# precharger_rev3.net
KiCad netlist of a schematic drawn in EAGLE
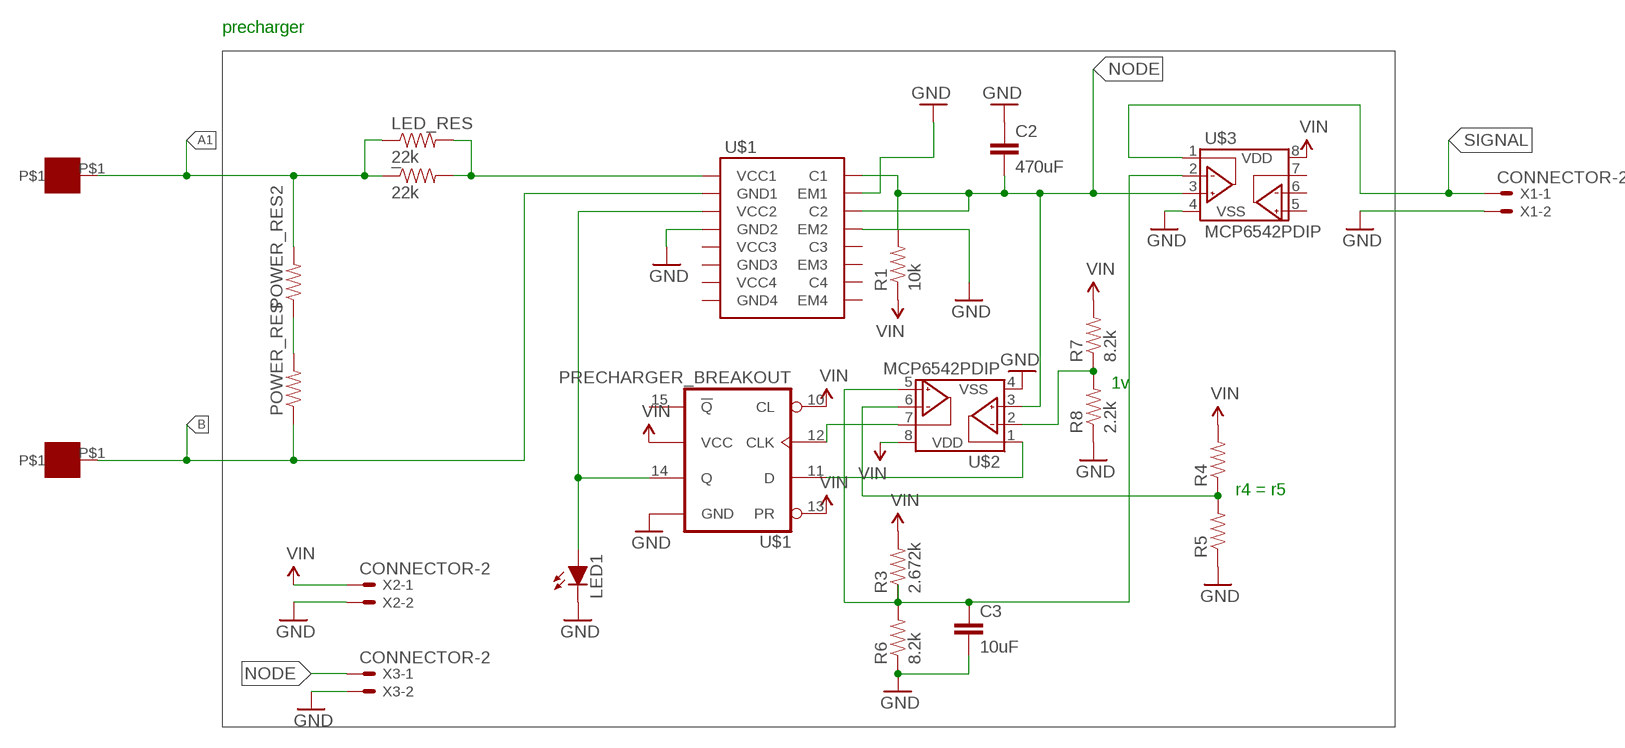
[diagram p0: schematic, sheet 1]

(export (version "E")
  (design (tool "Eeschema 10.0.6"))
  (components
    (comp (ref "+")
      (value "SOLDER_PAD")
      (footprint "eagle-import:SOLDER_PAD_XSMALL")
      (libsource (lib "eagle-import") (part "SOLDER_PAD"))
    )
    (comp (ref "-")
      (value "SOLDER_PAD")
      (footprint "eagle-import:SOLDER_PAD_XSMALL")
      (libsource (lib "eagle-import") (part "SOLDER_PAD"))
    )
    (comp (ref "C2")
      (value "470uF")
      (footprint "eagle-import:CAP-PTH-5MM")
      (libsource (lib "eagle-import") (part "CAPPTH1"))
    )
    (comp (ref "C3")
      (value "10uF")
      (footprint "eagle-import:CAP-PTH-SMALL")
      (libsource (lib "eagle-import") (part "CAPPTH"))
    )
    (comp (ref "LED1")
      (value "LED-3MM")
      (footprint "eagle-import:LED-3MM")
      (libsource (lib "eagle-import") (part "LED-3MM"))
    )
    (comp (ref "LED_RES")
      (value "22k")
      (footprint "eagle-import:AXIAL-0.3")
      (libsource (lib "eagle-import") (part "RESISTORAXIAL-0.3"))
    )
    (comp (ref "POWER_RES")
      (value "RESISTOR10W")
      (footprint "eagle-import:10W_RESISTOR_VISHAY")
      (libsource (lib "eagle-import") (part "RESISTOR10W"))
    )
    (comp (ref "POWER_RES2")
      (value "RESISTOR10W")
      (footprint "eagle-import:10W_RESISTOR_VISHAY")
      (libsource (lib "eagle-import") (part "RESISTOR10W"))
    )
    (comp (ref "R1")
      (value "10k")
      (footprint "eagle-import:AXIAL-0.3")
      (libsource (lib "eagle-import") (part "RESISTORAXIAL-0.3"))
    )
    (comp (ref "R3")
      (value "2.672k")
      (footprint "eagle-import:AXIAL-0.3")
      (libsource (lib "eagle-import") (part "RESISTORAXIAL-0.3"))
    )
    (comp (ref "R4")
      (value "RESISTORAXIAL-0.3")
      (footprint "eagle-import:AXIAL-0.3")
      (libsource (lib "eagle-import") (part "RESISTORAXIAL-0.3"))
    )
    (comp (ref "R5")
      (value "RESISTORAXIAL-0.3")
      (footprint "eagle-import:AXIAL-0.3")
      (libsource (lib "eagle-import") (part "RESISTORAXIAL-0.3"))
    )
    (comp (ref "R6")
      (value "8.2k")
      (footprint "eagle-import:AXIAL-0.3")
      (libsource (lib "eagle-import") (part "RESISTORAXIAL-0.3"))
    )
    (comp (ref "R7")
      (value "8.2k")
      (footprint "eagle-import:AXIAL-0.3")
      (libsource (lib "eagle-import") (part "RESISTORAXIAL-0.3"))
    )
    (comp (ref "R8")
      (value "2.2k")
      (footprint "eagle-import:AXIAL-0.3")
      (libsource (lib "eagle-import") (part "RESISTORAXIAL-0.3"))
    )
    (comp (ref "U$1")
      (value "PRECHARGER_BREAKOUT")
      (footprint "eagle-import:PRECHARGER_BREAKOUT")
      (libsource (lib "eagle-import") (part "PRECHARGER_BREAKOUT"))
    )
    (comp (ref "U$2")
      (value "MCP6542PDIP")
      (footprint "eagle-import:DIL08")
      (libsource (lib "eagle-import") (part "MCP6542PDIP"))
    )
    (comp (ref "U$3")
      (value "MCP6542PDIP")
      (footprint "eagle-import:DIL08")
      (libsource (lib "eagle-import") (part "MCP6542PDIP"))
    )
    (comp (ref "X1")
      (value "CONNECTOR-2")
      (footprint "eagle-import:MINIFIT_5566-2")
      (libsource (lib "eagle-import") (part "CONNECTOR-2"))
    )
    (comp (ref "X2")
      (value "CONNECTOR-2")
      (footprint "eagle-import:MINIFIT_5566-2")
      (libsource (lib "eagle-import") (part "CONNECTOR-2"))
    )
    (comp (ref "X3")
      (value "CONNECTOR-2")
      (footprint "eagle-import:MINIFIT_5566-2")
      (libsource (lib "eagle-import") (part "CONNECTOR-2"))
    )
    (comp (ref "_")
      (value "22k")
      (footprint "eagle-import:AXIAL-0.3")
      (libsource (lib "eagle-import") (part "RESISTORAXIAL-0.3"))
    )
  )
  (nets
    (net (code "1") (name "A1") (class "Default")
      (node (ref "+") (pin "P$1") (pinfunction "P$1_P$1") (pintype "bidirectional"))
      (node (ref "LED_RES") (pin "P$1") (pinfunction "1_P$1") (pintype "passive"))
      (node (ref "POWER_RES2") (pin "2") (pinfunction "2_2") (pintype "passive"))
      (node (ref "_") (pin "P$1") (pinfunction "1_P$1") (pintype "passive"))
    )
    (net (code "2") (name "B") (class "Default")
      (node (ref "-") (pin "P$1") (pinfunction "P$1_P$1") (pintype "bidirectional"))
      (node (ref "POWER_RES") (pin "1") (pinfunction "1_1") (pintype "passive"))
      (node (ref "U$1") (pin "2") (pinfunction "GND1_2") (pintype "passive"))
    )
    (net (code "3") (name "GND") (class "Default")
      (node (ref "C2") (pin "1") (pinfunction "1_1") (pintype "passive"))
      (node (ref "C3") (pin "2") (pinfunction "2_2") (pintype "passive"))
      (node (ref "LED1") (pin "K") (pinfunction "C_K") (pintype "passive"))
      (node (ref "R5") (pin "P$1") (pinfunction "1_P$1") (pintype "passive"))
      (node (ref "R6") (pin "P$1") (pinfunction "1_P$1") (pintype "passive"))
      (node (ref "R8") (pin "P$1") (pinfunction "1_P$1") (pintype "passive"))
      (node (ref "U$1") (pin "16") (pinfunction "GND_16") (pintype "bidirectional"))
      (node (ref "U$1") (pin "29") (pinfunction "EM2_29") (pintype "passive"))
      (node (ref "U$1") (pin "31") (pinfunction "EM1_31") (pintype "passive"))
      (node (ref "U$1") (pin "4") (pinfunction "GND2_4") (pintype "passive"))
      (node (ref "U$2") (pin "4") (pinfunction "VSS_4") (pintype "passive"))
      (node (ref "U$3") (pin "4") (pinfunction "VSS_4") (pintype "passive"))
      (node (ref "X1") (pin "2") (pinfunction "S_2") (pintype "passive"))
      (node (ref "X2") (pin "2") (pinfunction "S_2") (pintype "passive"))
      (node (ref "X3") (pin "2") (pinfunction "S_2") (pintype "passive"))
    )
    (net (code "4") (name "NODE") (class "Default")
      (node (ref "C2") (pin "2") (pinfunction "2_2") (pintype "passive"))
      (node (ref "R1") (pin "P$2") (pinfunction "2_P$2") (pintype "passive"))
      (node (ref "U$1") (pin "30") (pinfunction "C2_30") (pintype "passive"))
      (node (ref "U$1") (pin "32") (pinfunction "C1_32") (pintype "passive"))
      (node (ref "U$2") (pin "3") (pinfunction "VINA+_3") (pintype "passive"))
      (node (ref "U$3") (pin "3") (pinfunction "VINA+_3") (pintype "passive"))
      (node (ref "X3") (pin "1") (pinfunction "S_1") (pintype "passive"))
    )
    (net (code "5") (name "Net-(LED_RES-2)") (class "Default")
      (node (ref "LED_RES") (pin "P$2") (pinfunction "2_P$2") (pintype "passive"))
      (node (ref "U$1") (pin "1") (pinfunction "VCC1_1") (pintype "passive"))
      (node (ref "_") (pin "P$2") (pinfunction "2_P$2") (pintype "passive"))
    )
    (net (code "6") (name "Net-(POWER_RES-Pad2)") (class "Default")
      (node (ref "POWER_RES") (pin "2") (pinfunction "2_2") (pintype "passive"))
      (node (ref "POWER_RES2") (pin "1") (pinfunction "1_1") (pintype "passive"))
    )
    (net (code "7") (name "Net-(R3-1)") (class "Default")
      (node (ref "C3") (pin "1") (pinfunction "1_1") (pintype "passive"))
      (node (ref "R3") (pin "P$1") (pinfunction "1_P$1") (pintype "passive"))
      (node (ref "R6") (pin "P$2") (pinfunction "2_P$2") (pintype "passive"))
      (node (ref "U$2") (pin "5") (pinfunction "VINB+_5") (pintype "passive"))
      (node (ref "U$3") (pin "2") (pinfunction "VINA-_2") (pintype "passive"))
    )
    (net (code "8") (name "Net-(R4-1)") (class "Default")
      (node (ref "R4") (pin "P$1") (pinfunction "1_P$1") (pintype "passive"))
      (node (ref "R5") (pin "P$2") (pinfunction "2_P$2") (pintype "passive"))
      (node (ref "U$2") (pin "6") (pinfunction "VINB-_6") (pintype "passive"))
    )
    (net (code "9") (name "Net-(R7-1)") (class "Default")
      (node (ref "R7") (pin "P$1") (pinfunction "1_P$1") (pintype "passive"))
      (node (ref "R8") (pin "P$2") (pinfunction "2_P$2") (pintype "passive"))
      (node (ref "U$2") (pin "2") (pinfunction "VINA-_2") (pintype "passive"))
    )
    (net (code "10") (name "Net-(U$1-CLK)") (class "Default")
      (node (ref "U$1") (pin "12") (pinfunction "CLK_12") (pintype "input"))
      (node (ref "U$2") (pin "7") (pinfunction "VOUTB_7") (pintype "passive"))
    )
    (net (code "11") (name "Net-(U$1-D)") (class "Default")
      (node (ref "U$1") (pin "11") (pinfunction "D_11") (pintype "input"))
      (node (ref "U$2") (pin "1") (pinfunction "VOUTA_1") (pintype "passive"))
    )
    (net (code "12") (name "Net-(U$1-Q)") (class "Default")
      (node (ref "LED1") (pin "A") (pinfunction "A_A") (pintype "passive"))
      (node (ref "U$1") (pin "14") (pinfunction "Q_14") (pintype "output"))
      (node (ref "U$1") (pin "3") (pinfunction "VCC2_3") (pintype "passive"))
    )
    (net (code "13") (name "SIGNAL") (class "Default")
      (node (ref "U$3") (pin "1") (pinfunction "VOUTA_1") (pintype "passive"))
      (node (ref "X1") (pin "1") (pinfunction "S_1") (pintype "passive"))
    )
    (net (code "14") (name "VIN") (class "Default")
      (node (ref "R1") (pin "P$1") (pinfunction "1_P$1") (pintype "passive"))
      (node (ref "R3") (pin "P$2") (pinfunction "2_P$2") (pintype "passive"))
      (node (ref "R4") (pin "P$2") (pinfunction "2_P$2") (pintype "passive"))
      (node (ref "R7") (pin "P$2") (pinfunction "2_P$2") (pintype "passive"))
      (node (ref "U$1") (pin "10") (pinfunction "CL_10") (pintype "input"))
      (node (ref "U$1") (pin "13") (pinfunction "PR_13") (pintype "input"))
      (node (ref "U$1") (pin "23") (pinfunction "VCC_23") (pintype "bidirectional"))
      (node (ref "U$2") (pin "8") (pinfunction "VDD_8") (pintype "passive"))
      (node (ref "U$3") (pin "8") (pinfunction "VDD_8") (pintype "passive"))
      (node (ref "X2") (pin "1") (pinfunction "S_1") (pintype "passive"))
    )
    (net (code "15") (name "unconnected-(U$1-C3-Pad28)") (class "Default")
      (node (ref "U$1") (pin "28") (pinfunction "C3_28") (pintype "passive"))
    )
    (net (code "16") (name "unconnected-(U$1-C4-Pad26)") (class "Default")
      (node (ref "U$1") (pin "26") (pinfunction "C4_26") (pintype "passive"))
    )
    (net (code "17") (name "unconnected-(U$1-EM3-Pad27)") (class "Default")
      (node (ref "U$1") (pin "27") (pinfunction "EM3_27") (pintype "passive"))
    )
    (net (code "18") (name "unconnected-(U$1-EM4-Pad25)") (class "Default")
      (node (ref "U$1") (pin "25") (pinfunction "EM4_25") (pintype "passive"))
    )
    (net (code "19") (name "unconnected-(U$1-GND3-Pad6)") (class "Default")
      (node (ref "U$1") (pin "6") (pinfunction "GND3_6") (pintype "passive"))
    )
    (net (code "20") (name "unconnected-(U$1-GND4-Pad8)") (class "Default")
      (node (ref "U$1") (pin "8") (pinfunction "GND4_8") (pintype "passive"))
    )
    (net (code "21") (name "unconnected-(U$1-VCC3-Pad5)") (class "Default")
      (node (ref "U$1") (pin "5") (pinfunction "VCC3_5") (pintype "passive"))
    )
    (net (code "22") (name "unconnected-(U$1-VCC4-Pad7)") (class "Default")
      (node (ref "U$1") (pin "7") (pinfunction "VCC4_7") (pintype "passive"))
    )
    (net (code "23") (name "unconnected-(U$1-~{Q}-Pad15)") (class "Default")
      (node (ref "U$1") (pin "15") (pinfunction "~{Q}_15") (pintype "output"))
    )
    (net (code "24") (name "unconnected-(U$3-VINB+-Pad5)") (class "Default")
      (node (ref "U$3") (pin "5") (pinfunction "VINB+_5") (pintype "passive"))
    )
    (net (code "25") (name "unconnected-(U$3-VINB--Pad6)") (class "Default")
      (node (ref "U$3") (pin "6") (pinfunction "VINB-_6") (pintype "passive"))
    )
    (net (code "26") (name "unconnected-(U$3-VOUTB-Pad7)") (class "Default")
      (node (ref "U$3") (pin "7") (pinfunction "VOUTB_7") (pintype "passive"))
    )
  )
)
